# LFR_IR.net
KiCad netlist of a schematic drawn in EasyEDA
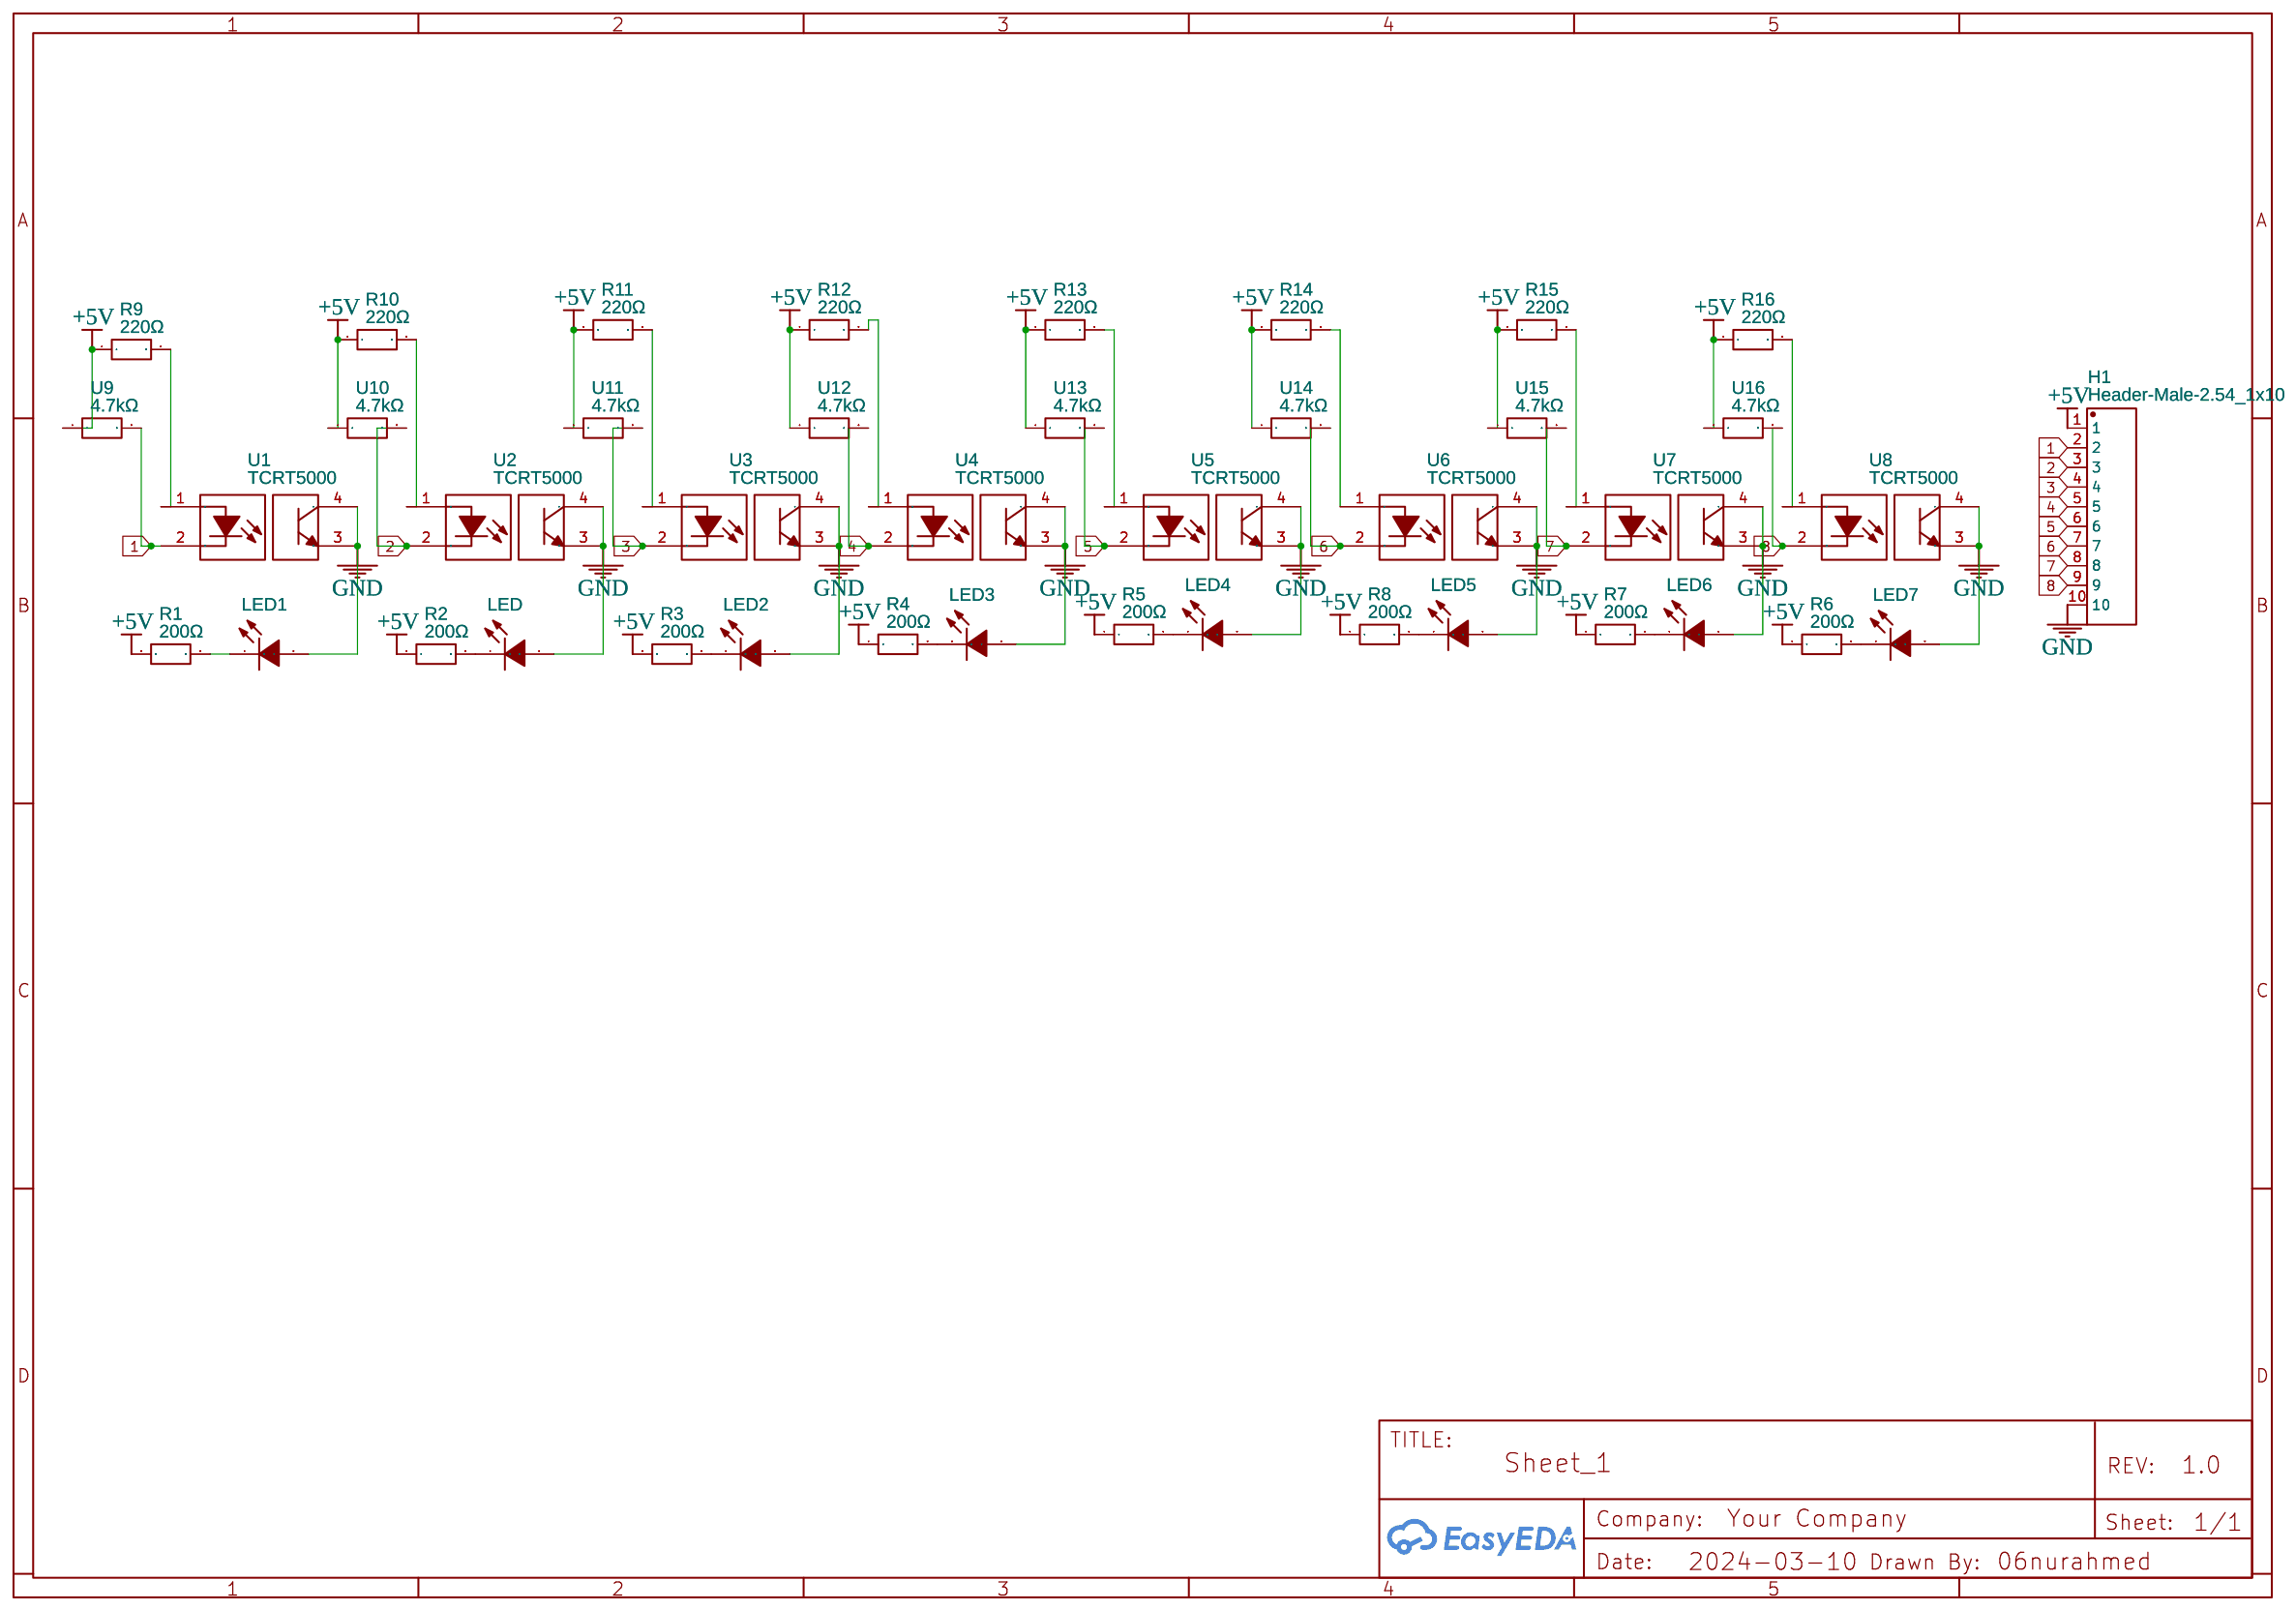
[diagram p0: schematic sheet]

(export (version "E")
  (design (tool "Eeschema 10.0.6"))
  (components
    (comp (ref "H1")
      (value "Header-Male-2.54_1x10")
      (fields (field (name "Manufacturer Part") "2.54-1*10P针") (field (name "Manufacturer") "BOOMELE(博穆精密)"))
      (libsource (lib "") (part "Header-Male-2.54_1x10"))
    )
    (comp (ref "LED") (value "LED-2835-白") (libsource (lib "") (part "LED-2835-白")))
    (comp (ref "LED1") (value "LED-2835-白") (libsource (lib "") (part "LED-2835-白")))
    (comp (ref "LED2") (value "LED-2835-白") (libsource (lib "") (part "LED-2835-白")))
    (comp (ref "LED3") (value "LED-2835-白") (libsource (lib "") (part "LED-2835-白")))
    (comp (ref "LED4") (value "LED-2835-白") (libsource (lib "") (part "LED-2835-白")))
    (comp (ref "LED5") (value "LED-2835-白") (libsource (lib "") (part "LED-2835-白")))
    (comp (ref "LED6") (value "LED-2835-白") (libsource (lib "") (part "LED-2835-白")))
    (comp (ref "LED7") (value "LED-2835-白") (libsource (lib "") (part "LED-2835-白")))
    (comp (ref "R1")
      (value "200Ω")
      (fields (field (name "Manufacturer Part") "CR1/4W-200Ω±5%-ST52") (field (name "Manufacturer") "VO(翔胜)"))
      (libsource (lib "") (part "CR1/4W-200Ω±5%-ST52"))
    )
    (comp (ref "R2")
      (value "200Ω")
      (fields (field (name "Manufacturer Part") "CR1/4W-200Ω±5%-ST52") (field (name "Manufacturer") "VO(翔胜)"))
      (libsource (lib "") (part "CR1/4W-200Ω±5%-ST52"))
    )
    (comp (ref "R3")
      (value "200Ω")
      (fields (field (name "Manufacturer Part") "CR1/4W-200Ω±5%-ST52") (field (name "Manufacturer") "VO(翔胜)"))
      (libsource (lib "") (part "CR1/4W-200Ω±5%-ST52"))
    )
    (comp (ref "R4")
      (value "200Ω")
      (fields (field (name "Manufacturer Part") "CR1/4W-200Ω±5%-ST52") (field (name "Manufacturer") "VO(翔胜)"))
      (libsource (lib "") (part "CR1/4W-200Ω±5%-ST52"))
    )
    (comp (ref "R5")
      (value "200Ω")
      (fields (field (name "Manufacturer Part") "CR1/4W-200Ω±5%-ST52") (field (name "Manufacturer") "VO(翔胜)"))
      (libsource (lib "") (part "CR1/4W-200Ω±5%-ST52"))
    )
    (comp (ref "R6")
      (value "200Ω")
      (fields (field (name "Manufacturer Part") "CR1/4W-200Ω±5%-ST52") (field (name "Manufacturer") "VO(翔胜)"))
      (libsource (lib "") (part "CR1/4W-200Ω±5%-ST52"))
    )
    (comp (ref "R7")
      (value "200Ω")
      (fields (field (name "Manufacturer Part") "CR1/4W-200Ω±5%-ST52") (field (name "Manufacturer") "VO(翔胜)"))
      (libsource (lib "") (part "CR1/4W-200Ω±5%-ST52"))
    )
    (comp (ref "R8")
      (value "200Ω")
      (fields (field (name "Manufacturer Part") "CR1/4W-200Ω±5%-ST52") (field (name "Manufacturer") "VO(翔胜)"))
      (libsource (lib "") (part "CR1/4W-200Ω±5%-ST52"))
    )
    (comp (ref "R9")
      (value "220Ω")
      (fields (field (name "Manufacturer Part") "CR1/4W-220Ω±5%-ST52") (field (name "Manufacturer") "VO(翔胜)"))
      (libsource (lib "") (part "CR1/4W-220Ω±5%-ST52"))
    )
    (comp (ref "R10")
      (value "220Ω")
      (fields (field (name "Manufacturer Part") "CR1/4W-220Ω±5%-ST52") (field (name "Manufacturer") "VO(翔胜)"))
      (libsource (lib "") (part "CR1/4W-220Ω±5%-ST52"))
    )
    (comp (ref "R11")
      (value "220Ω")
      (fields (field (name "Manufacturer Part") "CR1/4W-220Ω±5%-ST52") (field (name "Manufacturer") "VO(翔胜)"))
      (libsource (lib "") (part "CR1/4W-220Ω±5%-ST52"))
    )
    (comp (ref "R12")
      (value "220Ω")
      (fields (field (name "Manufacturer Part") "CR1/4W-220Ω±5%-ST52") (field (name "Manufacturer") "VO(翔胜)"))
      (libsource (lib "") (part "CR1/4W-220Ω±5%-ST52"))
    )
    (comp (ref "R13")
      (value "220Ω")
      (fields (field (name "Manufacturer Part") "CR1/4W-220Ω±5%-ST52") (field (name "Manufacturer") "VO(翔胜)"))
      (libsource (lib "") (part "CR1/4W-220Ω±5%-ST52"))
    )
    (comp (ref "R14")
      (value "220Ω")
      (fields (field (name "Manufacturer Part") "CR1/4W-220Ω±5%-ST52") (field (name "Manufacturer") "VO(翔胜)"))
      (libsource (lib "") (part "CR1/4W-220Ω±5%-ST52"))
    )
    (comp (ref "R15")
      (value "220Ω")
      (fields (field (name "Manufacturer Part") "CR1/4W-220Ω±5%-ST52") (field (name "Manufacturer") "VO(翔胜)"))
      (libsource (lib "") (part "CR1/4W-220Ω±5%-ST52"))
    )
    (comp (ref "R16")
      (value "220Ω")
      (fields (field (name "Manufacturer Part") "CR1/4W-220Ω±5%-ST52") (field (name "Manufacturer") "VO(翔胜)"))
      (libsource (lib "") (part "CR1/4W-220Ω±5%-ST52"))
    )
    (comp (ref "U1")
      (value "TCRT5000")
      (fields (field (name "Manufacturer") "VISHAY(威世)"))
      (libsource (lib "") (part "TCRT5000"))
    )
    (comp (ref "U2")
      (value "TCRT5000")
      (fields (field (name "Manufacturer") "VISHAY(威世)"))
      (libsource (lib "") (part "TCRT5000"))
    )
    (comp (ref "U3")
      (value "TCRT5000")
      (fields (field (name "Manufacturer") "VISHAY(威世)"))
      (libsource (lib "") (part "TCRT5000"))
    )
    (comp (ref "U4")
      (value "TCRT5000")
      (fields (field (name "Manufacturer") "VISHAY(威世)"))
      (libsource (lib "") (part "TCRT5000"))
    )
    (comp (ref "U5")
      (value "TCRT5000")
      (fields (field (name "Manufacturer") "VISHAY(威世)"))
      (libsource (lib "") (part "TCRT5000"))
    )
    (comp (ref "U6")
      (value "TCRT5000")
      (fields (field (name "Manufacturer") "VISHAY(威世)"))
      (libsource (lib "") (part "TCRT5000"))
    )
    (comp (ref "U7")
      (value "TCRT5000")
      (fields (field (name "Manufacturer") "VISHAY(威世)"))
      (libsource (lib "") (part "TCRT5000"))
    )
    (comp (ref "U8")
      (value "TCRT5000")
      (fields (field (name "Manufacturer") "VISHAY(威世)"))
      (libsource (lib "") (part "TCRT5000"))
    )
    (comp (ref "U9")
      (value "4.7kΩ")
      (fields (field (name "Manufacturer Part") "CR1/4W-4K7±5%-ST52") (field (name "Manufacturer") "VO(翔胜)"))
      (libsource (lib "") (part "CR1/4W-4K7±5%-ST52"))
    )
    (comp (ref "U10")
      (value "4.7kΩ")
      (fields (field (name "Manufacturer Part") "CR1/4W-4K7±5%-ST52") (field (name "Manufacturer") "VO(翔胜)"))
      (libsource (lib "") (part "CR1/4W-4K7±5%-ST52"))
    )
    (comp (ref "U11")
      (value "4.7kΩ")
      (fields (field (name "Manufacturer Part") "CR1/4W-4K7±5%-ST52") (field (name "Manufacturer") "VO(翔胜)"))
      (libsource (lib "") (part "CR1/4W-4K7±5%-ST52"))
    )
    (comp (ref "U12")
      (value "4.7kΩ")
      (fields (field (name "Manufacturer Part") "CR1/4W-4K7±5%-ST52") (field (name "Manufacturer") "VO(翔胜)"))
      (libsource (lib "") (part "CR1/4W-4K7±5%-ST52"))
    )
    (comp (ref "U13")
      (value "4.7kΩ")
      (fields (field (name "Manufacturer Part") "CR1/4W-4K7±5%-ST52") (field (name "Manufacturer") "VO(翔胜)"))
      (libsource (lib "") (part "CR1/4W-4K7±5%-ST52"))
    )
    (comp (ref "U14")
      (value "4.7kΩ")
      (fields (field (name "Manufacturer Part") "CR1/4W-4K7±5%-ST52") (field (name "Manufacturer") "VO(翔胜)"))
      (libsource (lib "") (part "CR1/4W-4K7±5%-ST52"))
    )
    (comp (ref "U15")
      (value "4.7kΩ")
      (fields (field (name "Manufacturer Part") "CR1/4W-4K7±5%-ST52") (field (name "Manufacturer") "VO(翔胜)"))
      (libsource (lib "") (part "CR1/4W-4K7±5%-ST52"))
    )
    (comp (ref "U16")
      (value "4.7kΩ")
      (fields (field (name "Manufacturer Part") "CR1/4W-4K7±5%-ST52") (field (name "Manufacturer") "VO(翔胜)"))
      (libsource (lib "") (part "CR1/4W-4K7±5%-ST52"))
    )
  )
  (nets
    (net (code "1") (name "+5V") (class "Default")
      (node (ref "H1") (pin "1") (pinfunction "1_1") (pintype "unspecified"))
      (node (ref "R1") (pin "1") (pinfunction "1_1") (pintype "unspecified"))
      (node (ref "R10") (pin "1") (pinfunction "1_1") (pintype "unspecified"))
      (node (ref "R11") (pin "1") (pinfunction "1_1") (pintype "unspecified"))
      (node (ref "R12") (pin "1") (pinfunction "1_1") (pintype "unspecified"))
      (node (ref "R13") (pin "1") (pinfunction "1_1") (pintype "unspecified"))
      (node (ref "R14") (pin "1") (pinfunction "1_1") (pintype "unspecified"))
      (node (ref "R15") (pin "1") (pinfunction "1_1") (pintype "unspecified"))
      (node (ref "R16") (pin "1") (pinfunction "1_1") (pintype "unspecified"))
      (node (ref "R2") (pin "1") (pinfunction "1_1") (pintype "unspecified"))
      (node (ref "R3") (pin "1") (pinfunction "1_1") (pintype "unspecified"))
      (node (ref "R4") (pin "1") (pinfunction "1_1") (pintype "unspecified"))
      (node (ref "R5") (pin "1") (pinfunction "1_1") (pintype "unspecified"))
      (node (ref "R6") (pin "1") (pinfunction "1_1") (pintype "unspecified"))
      (node (ref "R7") (pin "1") (pinfunction "1_1") (pintype "unspecified"))
      (node (ref "R8") (pin "1") (pinfunction "1_1") (pintype "unspecified"))
      (node (ref "R9") (pin "1") (pinfunction "1_1") (pintype "unspecified"))
      (node (ref "U10") (pin "1") (pinfunction "1_1") (pintype "unspecified"))
      (node (ref "U11") (pin "1") (pinfunction "1_1") (pintype "unspecified"))
      (node (ref "U12") (pin "1") (pinfunction "1_1") (pintype "unspecified"))
      (node (ref "U13") (pin "1") (pinfunction "1_1") (pintype "unspecified"))
      (node (ref "U14") (pin "1") (pinfunction "1_1") (pintype "unspecified"))
      (node (ref "U15") (pin "1") (pinfunction "1_1") (pintype "unspecified"))
      (node (ref "U16") (pin "1") (pinfunction "1_1") (pintype "unspecified"))
      (node (ref "U9") (pin "1") (pinfunction "1_1") (pintype "unspecified"))
    )
    (net (code "2") (name "1") (class "Default")
      (node (ref "H1") (pin "2") (pinfunction "2_2") (pintype "unspecified"))
      (node (ref "U1") (pin "2") (pinfunction "2_2") (pintype "unspecified"))
      (node (ref "U9") (pin "2") (pinfunction "2_2") (pintype "unspecified"))
    )
    (net (code "3") (name "2") (class "Default")
      (node (ref "H1") (pin "3") (pinfunction "3_3") (pintype "unspecified"))
      (node (ref "U10") (pin "2") (pinfunction "2_2") (pintype "unspecified"))
      (node (ref "U2") (pin "2") (pinfunction "2_2") (pintype "unspecified"))
    )
    (net (code "4") (name "3") (class "Default")
      (node (ref "H1") (pin "4") (pinfunction "4_4") (pintype "unspecified"))
      (node (ref "U11") (pin "2") (pinfunction "2_2") (pintype "unspecified"))
      (node (ref "U3") (pin "2") (pinfunction "2_2") (pintype "unspecified"))
    )
    (net (code "5") (name "4") (class "Default")
      (node (ref "H1") (pin "5") (pinfunction "5_5") (pintype "unspecified"))
      (node (ref "U12") (pin "2") (pinfunction "2_2") (pintype "unspecified"))
      (node (ref "U4") (pin "2") (pinfunction "2_2") (pintype "unspecified"))
    )
    (net (code "6") (name "5") (class "Default")
      (node (ref "H1") (pin "6") (pinfunction "6_6") (pintype "unspecified"))
      (node (ref "U13") (pin "2") (pinfunction "2_2") (pintype "unspecified"))
      (node (ref "U5") (pin "2") (pinfunction "2_2") (pintype "unspecified"))
    )
    (net (code "7") (name "6") (class "Default")
      (node (ref "H1") (pin "7") (pinfunction "7_7") (pintype "unspecified"))
      (node (ref "U14") (pin "2") (pinfunction "2_2") (pintype "unspecified"))
      (node (ref "U6") (pin "2") (pinfunction "2_2") (pintype "unspecified"))
    )
    (net (code "8") (name "7") (class "Default")
      (node (ref "H1") (pin "8") (pinfunction "8_8") (pintype "unspecified"))
      (node (ref "U15") (pin "2") (pinfunction "2_2") (pintype "unspecified"))
      (node (ref "U7") (pin "2") (pinfunction "2_2") (pintype "unspecified"))
    )
    (net (code "9") (name "8") (class "Default")
      (node (ref "H1") (pin "9") (pinfunction "9_9") (pintype "unspecified"))
      (node (ref "U16") (pin "2") (pinfunction "2_2") (pintype "unspecified"))
      (node (ref "U8") (pin "2") (pinfunction "2_2") (pintype "unspecified"))
    )
    (net (code "10") (name "GND") (class "Default")
      (node (ref "H1") (pin "10") (pinfunction "10_10") (pintype "unspecified"))
      (node (ref "LED") (pin "2") (pinfunction "A_2") (pintype "unspecified"))
      (node (ref "LED1") (pin "2") (pinfunction "A_2") (pintype "unspecified"))
      (node (ref "LED2") (pin "2") (pinfunction "A_2") (pintype "unspecified"))
      (node (ref "LED3") (pin "2") (pinfunction "A_2") (pintype "unspecified"))
      (node (ref "LED4") (pin "2") (pinfunction "A_2") (pintype "unspecified"))
      (node (ref "LED5") (pin "2") (pinfunction "A_2") (pintype "unspecified"))
      (node (ref "LED6") (pin "2") (pinfunction "A_2") (pintype "unspecified"))
      (node (ref "LED7") (pin "2") (pinfunction "A_2") (pintype "unspecified"))
      (node (ref "U1") (pin "3") (pinfunction "3_3") (pintype "unspecified"))
      (node (ref "U1") (pin "4") (pinfunction "4_4") (pintype "unspecified"))
      (node (ref "U2") (pin "3") (pinfunction "3_3") (pintype "unspecified"))
      (node (ref "U2") (pin "4") (pinfunction "4_4") (pintype "unspecified"))
      (node (ref "U3") (pin "3") (pinfunction "3_3") (pintype "unspecified"))
      (node (ref "U3") (pin "4") (pinfunction "4_4") (pintype "unspecified"))
      (node (ref "U4") (pin "3") (pinfunction "3_3") (pintype "unspecified"))
      (node (ref "U4") (pin "4") (pinfunction "4_4") (pintype "unspecified"))
      (node (ref "U5") (pin "3") (pinfunction "3_3") (pintype "unspecified"))
      (node (ref "U5") (pin "4") (pinfunction "4_4") (pintype "unspecified"))
      (node (ref "U6") (pin "3") (pinfunction "3_3") (pintype "unspecified"))
      (node (ref "U6") (pin "4") (pinfunction "4_4") (pintype "unspecified"))
      (node (ref "U7") (pin "3") (pinfunction "3_3") (pintype "unspecified"))
      (node (ref "U7") (pin "4") (pinfunction "4_4") (pintype "unspecified"))
      (node (ref "U8") (pin "3") (pinfunction "3_3") (pintype "unspecified"))
      (node (ref "U8") (pin "4") (pinfunction "4_4") (pintype "unspecified"))
    )
    (net (code "11") (name "Net-(LED-C)") (class "Default")
      (node (ref "LED") (pin "1") (pinfunction "C_1") (pintype "unspecified"))
      (node (ref "R2") (pin "2") (pinfunction "2_2") (pintype "unspecified"))
    )
    (net (code "12") (name "Net-(LED1-C)") (class "Default")
      (node (ref "LED1") (pin "1") (pinfunction "C_1") (pintype "unspecified"))
      (node (ref "R1") (pin "2") (pinfunction "2_2") (pintype "unspecified"))
    )
    (net (code "13") (name "Net-(LED2-C)") (class "Default")
      (node (ref "LED2") (pin "1") (pinfunction "C_1") (pintype "unspecified"))
      (node (ref "R3") (pin "2") (pinfunction "2_2") (pintype "unspecified"))
    )
    (net (code "14") (name "Net-(LED3-C)") (class "Default")
      (node (ref "LED3") (pin "1") (pinfunction "C_1") (pintype "unspecified"))
      (node (ref "R4") (pin "2") (pinfunction "2_2") (pintype "unspecified"))
    )
    (net (code "15") (name "Net-(LED4-C)") (class "Default")
      (node (ref "LED4") (pin "1") (pinfunction "C_1") (pintype "unspecified"))
      (node (ref "R5") (pin "2") (pinfunction "2_2") (pintype "unspecified"))
    )
    (net (code "16") (name "Net-(LED5-C)") (class "Default")
      (node (ref "LED5") (pin "1") (pinfunction "C_1") (pintype "unspecified"))
      (node (ref "R8") (pin "2") (pinfunction "2_2") (pintype "unspecified"))
    )
    (net (code "17") (name "Net-(LED6-C)") (class "Default")
      (node (ref "LED6") (pin "1") (pinfunction "C_1") (pintype "unspecified"))
      (node (ref "R7") (pin "2") (pinfunction "2_2") (pintype "unspecified"))
    )
    (net (code "18") (name "Net-(LED7-C)") (class "Default")
      (node (ref "LED7") (pin "1") (pinfunction "C_1") (pintype "unspecified"))
      (node (ref "R6") (pin "2") (pinfunction "2_2") (pintype "unspecified"))
    )
    (net (code "19") (name "Net-(R9-Pad2)") (class "Default")
      (node (ref "R9") (pin "2") (pinfunction "2_2") (pintype "unspecified"))
      (node (ref "U1") (pin "1") (pinfunction "1_1") (pintype "unspecified"))
    )
    (net (code "20") (name "Net-(R10-Pad2)") (class "Default")
      (node (ref "R10") (pin "2") (pinfunction "2_2") (pintype "unspecified"))
      (node (ref "U2") (pin "1") (pinfunction "1_1") (pintype "unspecified"))
    )
    (net (code "21") (name "Net-(R11-Pad2)") (class "Default")
      (node (ref "R11") (pin "2") (pinfunction "2_2") (pintype "unspecified"))
      (node (ref "U3") (pin "1") (pinfunction "1_1") (pintype "unspecified"))
    )
    (net (code "22") (name "Net-(R12-Pad2)") (class "Default")
      (node (ref "R12") (pin "2") (pinfunction "2_2") (pintype "unspecified"))
      (node (ref "U4") (pin "1") (pinfunction "1_1") (pintype "unspecified"))
    )
    (net (code "23") (name "Net-(R13-Pad2)") (class "Default")
      (node (ref "R13") (pin "2") (pinfunction "2_2") (pintype "unspecified"))
      (node (ref "U5") (pin "1") (pinfunction "1_1") (pintype "unspecified"))
    )
    (net (code "24") (name "Net-(R14-Pad2)") (class "Default")
      (node (ref "R14") (pin "2") (pinfunction "2_2") (pintype "unspecified"))
      (node (ref "U6") (pin "1") (pinfunction "1_1") (pintype "unspecified"))
    )
    (net (code "25") (name "Net-(R15-Pad2)") (class "Default")
      (node (ref "R15") (pin "2") (pinfunction "2_2") (pintype "unspecified"))
      (node (ref "U7") (pin "1") (pinfunction "1_1") (pintype "unspecified"))
    )
    (net (code "26") (name "Net-(R16-Pad2)") (class "Default")
      (node (ref "R16") (pin "2") (pinfunction "2_2") (pintype "unspecified"))
      (node (ref "U8") (pin "1") (pinfunction "1_1") (pintype "unspecified"))
    )
  )
)
